# countdown.net
KiCad netlist of a schematic drawn in EAGLE
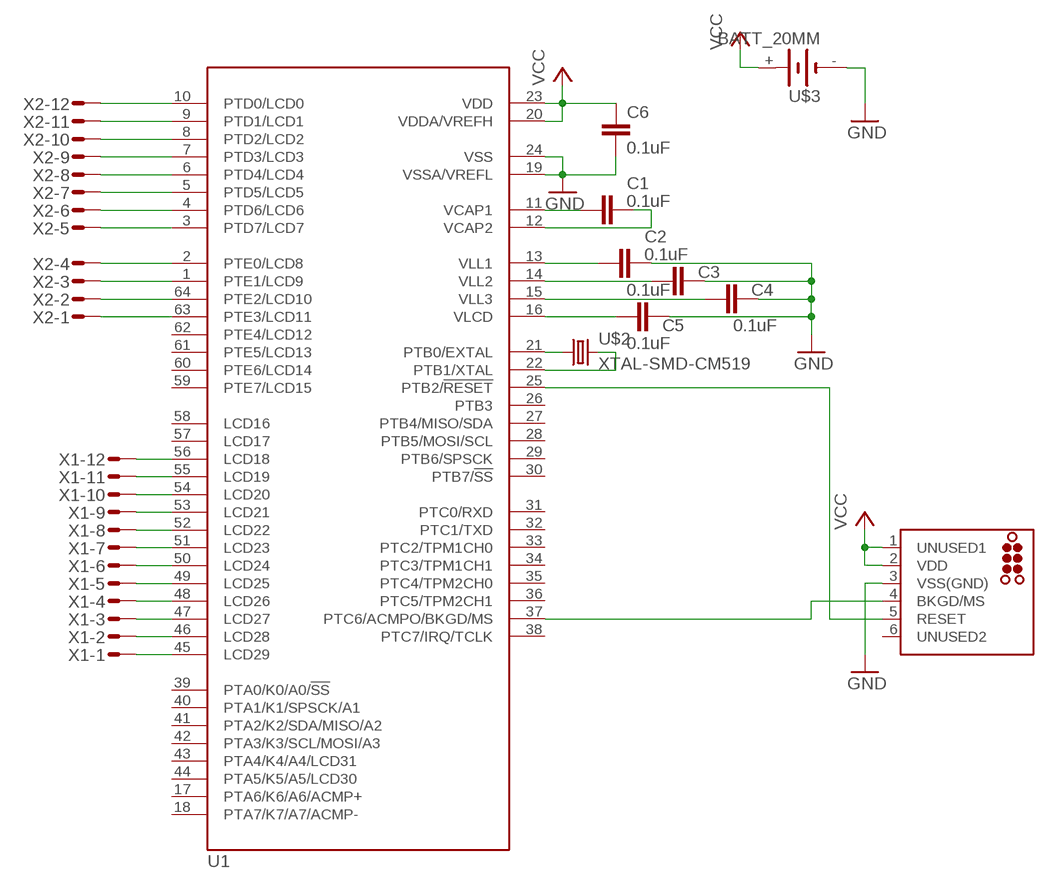
[diagram p0: schematic, sheet 1]

(export (version "E")
  (design (tool "Eeschema 10.0.6"))
  (components
    (comp (ref "BDM")
      (value "TC2030-MCP-NL")
      (footprint "eagle-import:TC2030-MCP-NL")
      (libsource (lib "eagle-import") (part "TC2030-MCP-NL"))
    )
    (comp (ref "C1")
      (value "0.1uF")
      (footprint "eagle-import:C0603K")
      (libsource (lib "eagle-import") (part "C-EUC0603K"))
    )
    (comp (ref "C2")
      (value "0.1uF")
      (footprint "eagle-import:C0603K")
      (libsource (lib "eagle-import") (part "C-EUC0603K"))
    )
    (comp (ref "C3")
      (value "0.1uF")
      (footprint "eagle-import:C0603K")
      (libsource (lib "eagle-import") (part "C-EUC0603K"))
    )
    (comp (ref "C4")
      (value "0.1uF")
      (footprint "eagle-import:C0603K")
      (libsource (lib "eagle-import") (part "C-EUC0603K"))
    )
    (comp (ref "C5")
      (value "0.1uF")
      (footprint "eagle-import:C0603K")
      (libsource (lib "eagle-import") (part "C-EUC0603K"))
    )
    (comp (ref "C6")
      (value "0.1uF")
      (footprint "eagle-import:C0603K")
      (libsource (lib "eagle-import") (part "C-EUC0603K"))
    )
    (comp (ref "U$2")
      (value "XTAL-SMD-CM519")
      (footprint "eagle-import:SMD-XTAL-CM519")
      (libsource (lib "eagle-import") (part "XTAL-SMD-CM519"))
    )
    (comp (ref "U$3")
      (value "BATT_20MM")
      (footprint "eagle-import:BATT_20MM")
      (libsource (lib "eagle-import") (part "BATT_20MM"))
    )
    (comp (ref "U1")
      (value "MC9S08LL16")
      (footprint "eagle-import:LQFP64")
      (libsource (lib "eagle-import") (part "MC9S08LL16"))
    )
    (comp (ref "X1-")
      (value "HEADER-12-EDGE")
      (footprint "eagle-import:HEADER-12-EDGE")
      (libsource (lib "eagle-import") (part "HEADER-12-EDGE"))
    )
    (comp (ref "X2-")
      (value "HEADER-12-EDGE")
      (footprint "eagle-import:HEADER-12-EDGE")
      (libsource (lib "eagle-import") (part "HEADER-12-EDGE"))
    )
  )
  (nets
    (net (code "1") (name "GND") (class "Default")
      (node (ref "BDM") (pin "3") (pinfunction "VSS(GND)_3") (pintype "power_in"))
      (node (ref "C2") (pin "1") (pinfunction "1_1") (pintype "passive"))
      (node (ref "C3") (pin "1") (pinfunction "1_1") (pintype "passive"))
      (node (ref "C4") (pin "1") (pinfunction "1_1") (pintype "passive"))
      (node (ref "C5") (pin "1") (pinfunction "1_1") (pintype "passive"))
      (node (ref "C6") (pin "2") (pinfunction "2_2") (pintype "passive"))
      (node (ref "U$3") (pin "-") (pinfunction "-_-") (pintype "passive"))
      (node (ref "U1") (pin "19") (pinfunction "VSSA/VREFL_19") (pintype "bidirectional"))
      (node (ref "U1") (pin "24") (pinfunction "VSS_24") (pintype "bidirectional"))
    )
    (net (code "2") (name "Net-(BDM-BKGD{slash}MS)") (class "Default")
      (node (ref "BDM") (pin "4") (pinfunction "BKGD/MS_4") (pintype "bidirectional"))
      (node (ref "U1") (pin "37") (pinfunction "PTC6/ACMPO/BKGD/MS_37") (pintype "bidirectional"))
    )
    (net (code "3") (name "Net-(BDM-RESET)") (class "Default")
      (node (ref "BDM") (pin "5") (pinfunction "RESET_5") (pintype "output"))
      (node (ref "U1") (pin "25") (pinfunction "PTB2/~{RESET}_25") (pintype "bidirectional"))
    )
    (net (code "4") (name "Net-(U$2-1)") (class "Default")
      (node (ref "U$2") (pin "P$1") (pinfunction "1_P$1") (pintype "passive"))
      (node (ref "U1") (pin "21") (pinfunction "PTB0/EXTAL_21") (pintype "bidirectional"))
    )
    (net (code "5") (name "Net-(U$2-2)") (class "Default")
      (node (ref "U$2") (pin "P$2") (pinfunction "2_P$2") (pintype "passive"))
      (node (ref "U1") (pin "22") (pinfunction "PTB1/XTAL_22") (pintype "bidirectional"))
    )
    (net (code "6") (name "Net-(U1-LCD18)") (class "Default")
      (node (ref "U1") (pin "56") (pinfunction "LCD18_56") (pintype "bidirectional"))
      (node (ref "X1-") (pin "12") (pinfunction "M_12") (pintype "passive"))
    )
    (net (code "7") (name "Net-(U1-LCD19)") (class "Default")
      (node (ref "U1") (pin "55") (pinfunction "LCD19_55") (pintype "bidirectional"))
      (node (ref "X1-") (pin "11") (pinfunction "M_11") (pintype "passive"))
    )
    (net (code "8") (name "Net-(U1-LCD20)") (class "Default")
      (node (ref "U1") (pin "54") (pinfunction "LCD20_54") (pintype "bidirectional"))
      (node (ref "X1-") (pin "10") (pinfunction "M_10") (pintype "passive"))
    )
    (net (code "9") (name "Net-(U1-LCD21)") (class "Default")
      (node (ref "U1") (pin "53") (pinfunction "LCD21_53") (pintype "bidirectional"))
      (node (ref "X1-") (pin "9") (pinfunction "M_9") (pintype "passive"))
    )
    (net (code "10") (name "Net-(U1-LCD22)") (class "Default")
      (node (ref "U1") (pin "52") (pinfunction "LCD22_52") (pintype "bidirectional"))
      (node (ref "X1-") (pin "8") (pinfunction "M_8") (pintype "passive"))
    )
    (net (code "11") (name "Net-(U1-LCD23)") (class "Default")
      (node (ref "U1") (pin "51") (pinfunction "LCD23_51") (pintype "bidirectional"))
      (node (ref "X1-") (pin "7") (pinfunction "M_7") (pintype "passive"))
    )
    (net (code "12") (name "Net-(U1-LCD24)") (class "Default")
      (node (ref "U1") (pin "50") (pinfunction "LCD24_50") (pintype "bidirectional"))
      (node (ref "X1-") (pin "6") (pinfunction "M_6") (pintype "passive"))
    )
    (net (code "13") (name "Net-(U1-LCD25)") (class "Default")
      (node (ref "U1") (pin "49") (pinfunction "LCD25_49") (pintype "bidirectional"))
      (node (ref "X1-") (pin "5") (pinfunction "M_5") (pintype "passive"))
    )
    (net (code "14") (name "Net-(U1-LCD26)") (class "Default")
      (node (ref "U1") (pin "48") (pinfunction "LCD26_48") (pintype "bidirectional"))
      (node (ref "X1-") (pin "4") (pinfunction "M_4") (pintype "passive"))
    )
    (net (code "15") (name "Net-(U1-LCD27)") (class "Default")
      (node (ref "U1") (pin "47") (pinfunction "LCD27_47") (pintype "bidirectional"))
      (node (ref "X1-") (pin "3") (pinfunction "M_3") (pintype "passive"))
    )
    (net (code "16") (name "Net-(U1-LCD28)") (class "Default")
      (node (ref "U1") (pin "46") (pinfunction "LCD28_46") (pintype "bidirectional"))
      (node (ref "X1-") (pin "2") (pinfunction "M_2") (pintype "passive"))
    )
    (net (code "17") (name "Net-(U1-LCD29)") (class "Default")
      (node (ref "U1") (pin "45") (pinfunction "LCD29_45") (pintype "bidirectional"))
      (node (ref "X1-") (pin "1") (pinfunction "M_1") (pintype "passive"))
    )
    (net (code "18") (name "Net-(U1-PTD0{slash}LCD0)") (class "Default")
      (node (ref "U1") (pin "10") (pinfunction "PTD0/LCD0_10") (pintype "bidirectional"))
      (node (ref "X2-") (pin "12") (pinfunction "M_12") (pintype "passive"))
    )
    (net (code "19") (name "Net-(U1-PTD1{slash}LCD1)") (class "Default")
      (node (ref "U1") (pin "9") (pinfunction "PTD1/LCD1_9") (pintype "bidirectional"))
      (node (ref "X2-") (pin "11") (pinfunction "M_11") (pintype "passive"))
    )
    (net (code "20") (name "Net-(U1-PTD2{slash}LCD2)") (class "Default")
      (node (ref "U1") (pin "8") (pinfunction "PTD2/LCD2_8") (pintype "bidirectional"))
      (node (ref "X2-") (pin "10") (pinfunction "M_10") (pintype "passive"))
    )
    (net (code "21") (name "Net-(U1-PTD3{slash}LCD3)") (class "Default")
      (node (ref "U1") (pin "7") (pinfunction "PTD3/LCD3_7") (pintype "bidirectional"))
      (node (ref "X2-") (pin "9") (pinfunction "M_9") (pintype "passive"))
    )
    (net (code "22") (name "Net-(U1-PTD4{slash}LCD4)") (class "Default")
      (node (ref "U1") (pin "6") (pinfunction "PTD4/LCD4_6") (pintype "bidirectional"))
      (node (ref "X2-") (pin "8") (pinfunction "M_8") (pintype "passive"))
    )
    (net (code "23") (name "Net-(U1-PTD5{slash}LCD5)") (class "Default")
      (node (ref "U1") (pin "5") (pinfunction "PTD5/LCD5_5") (pintype "bidirectional"))
      (node (ref "X2-") (pin "7") (pinfunction "M_7") (pintype "passive"))
    )
    (net (code "24") (name "Net-(U1-PTD6{slash}LCD6)") (class "Default")
      (node (ref "U1") (pin "4") (pinfunction "PTD6/LCD6_4") (pintype "bidirectional"))
      (node (ref "X2-") (pin "6") (pinfunction "M_6") (pintype "passive"))
    )
    (net (code "25") (name "Net-(U1-PTD7{slash}LCD7)") (class "Default")
      (node (ref "U1") (pin "3") (pinfunction "PTD7/LCD7_3") (pintype "bidirectional"))
      (node (ref "X2-") (pin "5") (pinfunction "M_5") (pintype "passive"))
    )
    (net (code "26") (name "Net-(U1-PTE0{slash}LCD8)") (class "Default")
      (node (ref "U1") (pin "2") (pinfunction "PTE0/LCD8_2") (pintype "bidirectional"))
      (node (ref "X2-") (pin "4") (pinfunction "M_4") (pintype "passive"))
    )
    (net (code "27") (name "Net-(U1-PTE1{slash}LCD9)") (class "Default")
      (node (ref "U1") (pin "1") (pinfunction "PTE1/LCD9_1") (pintype "bidirectional"))
      (node (ref "X2-") (pin "3") (pinfunction "M_3") (pintype "passive"))
    )
    (net (code "28") (name "Net-(U1-PTE2{slash}LCD10)") (class "Default")
      (node (ref "U1") (pin "64") (pinfunction "PTE2/LCD10_64") (pintype "bidirectional"))
      (node (ref "X2-") (pin "2") (pinfunction "M_2") (pintype "passive"))
    )
    (net (code "29") (name "Net-(U1-PTE3{slash}LCD11)") (class "Default")
      (node (ref "U1") (pin "63") (pinfunction "PTE3/LCD11_63") (pintype "bidirectional"))
      (node (ref "X2-") (pin "1") (pinfunction "M_1") (pintype "passive"))
    )
    (net (code "30") (name "Net-(U1-VCAP1)") (class "Default")
      (node (ref "C1") (pin "2") (pinfunction "2_2") (pintype "passive"))
      (node (ref "U1") (pin "11") (pinfunction "VCAP1_11") (pintype "bidirectional"))
    )
    (net (code "31") (name "Net-(U1-VCAP2)") (class "Default")
      (node (ref "C1") (pin "1") (pinfunction "1_1") (pintype "passive"))
      (node (ref "U1") (pin "12") (pinfunction "VCAP2_12") (pintype "bidirectional"))
    )
    (net (code "32") (name "Net-(U1-VLCD)") (class "Default")
      (node (ref "C5") (pin "2") (pinfunction "2_2") (pintype "passive"))
      (node (ref "U1") (pin "16") (pinfunction "VLCD_16") (pintype "bidirectional"))
    )
    (net (code "33") (name "Net-(U1-VLL1)") (class "Default")
      (node (ref "C2") (pin "2") (pinfunction "2_2") (pintype "passive"))
      (node (ref "U1") (pin "13") (pinfunction "VLL1_13") (pintype "bidirectional"))
    )
    (net (code "34") (name "Net-(U1-VLL2)") (class "Default")
      (node (ref "C3") (pin "2") (pinfunction "2_2") (pintype "passive"))
      (node (ref "U1") (pin "14") (pinfunction "VLL2_14") (pintype "bidirectional"))
    )
    (net (code "35") (name "Net-(U1-VLL3)") (class "Default")
      (node (ref "C4") (pin "2") (pinfunction "2_2") (pintype "passive"))
      (node (ref "U1") (pin "15") (pinfunction "VLL3_15") (pintype "bidirectional"))
    )
    (net (code "36") (name "VCC") (class "Default")
      (node (ref "BDM") (pin "1") (pinfunction "UNUSED1_1") (pintype "passive"))
      (node (ref "BDM") (pin "2") (pinfunction "VDD_2") (pintype "power_in"))
      (node (ref "C6") (pin "1") (pinfunction "1_1") (pintype "passive"))
      (node (ref "U$3") (pin "+") (pinfunction "+_+") (pintype "passive"))
      (node (ref "U1") (pin "20") (pinfunction "VDDA/VREFH_20") (pintype "bidirectional"))
      (node (ref "U1") (pin "23") (pinfunction "VDD_23") (pintype "bidirectional"))
    )
    (net (code "37") (name "unconnected-(BDM-UNUSED2-Pad6)") (class "Default")
      (node (ref "BDM") (pin "6") (pinfunction "UNUSED2_6") (pintype "bidirectional"))
    )
    (net (code "38") (name "unconnected-(U1-LCD16-Pad58)") (class "Default")
      (node (ref "U1") (pin "58") (pinfunction "LCD16_58") (pintype "bidirectional"))
    )
    (net (code "39") (name "unconnected-(U1-LCD17-Pad57)") (class "Default")
      (node (ref "U1") (pin "57") (pinfunction "LCD17_57") (pintype "bidirectional"))
    )
    (net (code "40") (name "unconnected-(U1-PTA0{slash}K0{slash}A0{slash}~{SS}-Pad39)") (class "Default")
      (node (ref "U1") (pin "39") (pinfunction "PTA0/K0/A0/~{SS}_39") (pintype "bidirectional"))
    )
    (net (code "41") (name "unconnected-(U1-PTA1{slash}K1{slash}SPSCK{slash}A1-Pad40)") (class "Default")
      (node (ref "U1") (pin "40") (pinfunction "PTA1/K1/SPSCK/A1_40") (pintype "bidirectional"))
    )
    (net (code "42") (name "unconnected-(U1-PTA2{slash}K2{slash}SDA{slash}MISO{slash}A2-Pad41)") (class "Default")
      (node (ref "U1") (pin "41") (pinfunction "PTA2/K2/SDA/MISO/A2_41") (pintype "bidirectional"))
    )
    (net (code "43") (name "unconnected-(U1-PTA3{slash}K3{slash}SCL{slash}MOSI{slash}A3-Pad42)") (class "Default")
      (node (ref "U1") (pin "42") (pinfunction "PTA3/K3/SCL/MOSI/A3_42") (pintype "bidirectional"))
    )
    (net (code "44") (name "unconnected-(U1-PTA4{slash}K4{slash}A4{slash}LCD31-Pad43)") (class "Default")
      (node (ref "U1") (pin "43") (pinfunction "PTA4/K4/A4/LCD31_43") (pintype "bidirectional"))
    )
    (net (code "45") (name "unconnected-(U1-PTA5{slash}K5{slash}A5{slash}LCD30-Pad44)") (class "Default")
      (node (ref "U1") (pin "44") (pinfunction "PTA5/K5/A5/LCD30_44") (pintype "bidirectional"))
    )
    (net (code "46") (name "unconnected-(U1-PTA6{slash}K6{slash}A6{slash}ACMP+-Pad17)") (class "Default")
      (node (ref "U1") (pin "17") (pinfunction "PTA6/K6/A6/ACMP+_17") (pintype "bidirectional"))
    )
    (net (code "47") (name "unconnected-(U1-PTA7{slash}K7{slash}A7{slash}ACMP--Pad18)") (class "Default")
      (node (ref "U1") (pin "18") (pinfunction "PTA7/K7/A7/ACMP-_18") (pintype "bidirectional"))
    )
    (net (code "48") (name "unconnected-(U1-PTB3-Pad26)") (class "Default")
      (node (ref "U1") (pin "26") (pinfunction "PTB3_26") (pintype "bidirectional"))
    )
    (net (code "49") (name "unconnected-(U1-PTB4{slash}MISO{slash}SDA-Pad27)") (class "Default")
      (node (ref "U1") (pin "27") (pinfunction "PTB4/MISO/SDA_27") (pintype "bidirectional"))
    )
    (net (code "50") (name "unconnected-(U1-PTB5{slash}MOSI{slash}SCL-Pad28)") (class "Default")
      (node (ref "U1") (pin "28") (pinfunction "PTB5/MOSI/SCL_28") (pintype "bidirectional"))
    )
    (net (code "51") (name "unconnected-(U1-PTB6{slash}SPSCK-Pad29)") (class "Default")
      (node (ref "U1") (pin "29") (pinfunction "PTB6/SPSCK_29") (pintype "bidirectional"))
    )
    (net (code "52") (name "unconnected-(U1-PTB7{slash}~{SS}-Pad30)") (class "Default")
      (node (ref "U1") (pin "30") (pinfunction "PTB7/~{SS}_30") (pintype "bidirectional"))
    )
    (net (code "53") (name "unconnected-(U1-PTC0{slash}RXD-Pad31)") (class "Default")
      (node (ref "U1") (pin "31") (pinfunction "PTC0/RXD_31") (pintype "bidirectional"))
    )
    (net (code "54") (name "unconnected-(U1-PTC1{slash}TXD-Pad32)") (class "Default")
      (node (ref "U1") (pin "32") (pinfunction "PTC1/TXD_32") (pintype "bidirectional"))
    )
    (net (code "55") (name "unconnected-(U1-PTC2{slash}TPM1CH0-Pad33)") (class "Default")
      (node (ref "U1") (pin "33") (pinfunction "PTC2/TPM1CH0_33") (pintype "bidirectional"))
    )
    (net (code "56") (name "unconnected-(U1-PTC3{slash}TPM1CH1-Pad34)") (class "Default")
      (node (ref "U1") (pin "34") (pinfunction "PTC3/TPM1CH1_34") (pintype "bidirectional"))
    )
    (net (code "57") (name "unconnected-(U1-PTC4{slash}TPM2CH0-Pad35)") (class "Default")
      (node (ref "U1") (pin "35") (pinfunction "PTC4/TPM2CH0_35") (pintype "bidirectional"))
    )
    (net (code "58") (name "unconnected-(U1-PTC5{slash}TPM2CH1-Pad36)") (class "Default")
      (node (ref "U1") (pin "36") (pinfunction "PTC5/TPM2CH1_36") (pintype "bidirectional"))
    )
    (net (code "59") (name "unconnected-(U1-PTC7{slash}IRQ{slash}TCLK-Pad38)") (class "Default")
      (node (ref "U1") (pin "38") (pinfunction "PTC7/IRQ/TCLK_38") (pintype "bidirectional"))
    )
    (net (code "60") (name "unconnected-(U1-PTE4{slash}LCD12-Pad62)") (class "Default")
      (node (ref "U1") (pin "62") (pinfunction "PTE4/LCD12_62") (pintype "bidirectional"))
    )
    (net (code "61") (name "unconnected-(U1-PTE5{slash}LCD13-Pad61)") (class "Default")
      (node (ref "U1") (pin "61") (pinfunction "PTE5/LCD13_61") (pintype "bidirectional"))
    )
    (net (code "62") (name "unconnected-(U1-PTE6{slash}LCD14-Pad60)") (class "Default")
      (node (ref "U1") (pin "60") (pinfunction "PTE6/LCD14_60") (pintype "bidirectional"))
    )
    (net (code "63") (name "unconnected-(U1-PTE7{slash}LCD15-Pad59)") (class "Default")
      (node (ref "U1") (pin "59") (pinfunction "PTE7/LCD15_59") (pintype "bidirectional"))
    )
  )
)
